# WemosESP8266.net
KiCad netlist of a schematic drawn in Altium Designer
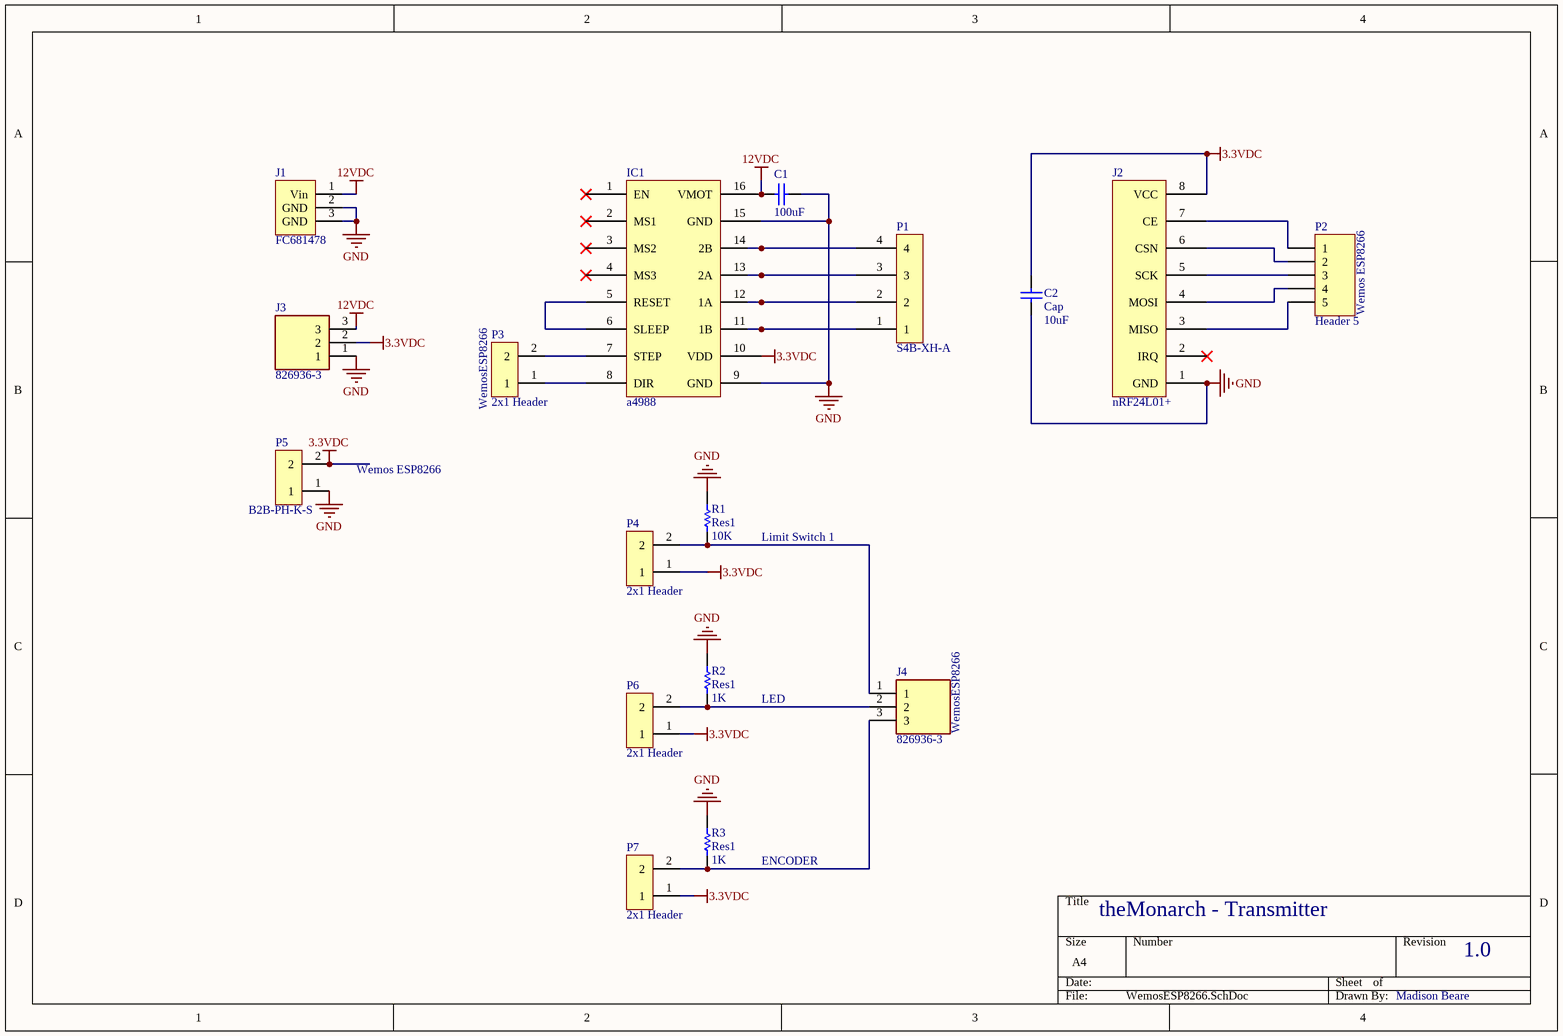
[diagram p0: WemosESP8266.SchDoc]

(export (version "E")
  (design (tool "Eeschema 10.0.6"))
  (components
    (comp (ref "C1")
      (value "100uF")
      (footprint "RAD-0.3")
      (description "Capacitor")
      (fields (field (name "PUBLISHER") "Altium Limited"))
      (libsource (lib "Miscellaneous Devices") (part "Cap"))
    )
    (comp (ref "C2")
      (value "Cap")
      (footprint "RAD-0.3")
      (description "Capacitor")
      (fields (field (name "ALTIUM_VALUE") "10uF") (field (name "PUBLISHER") "Altium Limited"))
      (libsource (lib "Miscellaneous Devices") (part "Cap"))
    )
    (comp (ref "IC1")
      (value "a4988")
      (footprint "MODULE_A4988_STEPPER_MOTOR_DRIVER_CARRIER")
      (libsource (lib "WemosESP8266_SchLib") (part "a4988"))
    )
    (comp (ref "J1")
      (value "FC681478")
      (footprint "FC681478")
      (description "CLIFF ELECTRONIC COMPONENTS         FC681478            CONNECTOR, POWER ENTRY, RCPT, 2A, 16VDC")
      (fields (field (name "MANUFACTURER") "Cliff"))
      (libsource (lib "WemosESP8266_SchLib") (part "FC681478"))
    )
    (comp (ref "J2")
      (value "nRF24L01+")
      (footprint "TE_5-146278-8")
      (description "SPARKFUN TRANSCEIVER BREAKOUT -")
      (fields (field (name "MANUFACTURER") "SparkFun") (field (name "MANUFACTURER PART NUMBER") "WRL-00691"))
      (libsource (lib "WemosESP8266_SchLib") (part "WRL-00691"))
    )
    (comp (ref "J3")
      (value "826936-3")
      (footprint "TE_826936-3")
      (description "Connector Header Through Hole 3 position 0.100 (2.54mm)")
      (fields (field (name "MF") "TE Connectivity"))
      (libsource (lib "") (part "826936-3_1"))
    )
    (comp (ref "J4")
      (value "826936-3")
      (footprint "TE_826936-3")
      (description "Connector Header Through Hole 3 position 0.100 (2.54mm)")
      (fields (field (name "MF") "TE Connectivity"))
      (libsource (lib "826936-3") (part "826936-3"))
    )
    (comp (ref "P1")
      (value "S4B-XH-A")
      (footprint "S4B-XH-A(LF)(SN)")
      (description "Conn Shrouded Header HDR 4 POS 2.5mm Solder RA Thru-Hole Box")
      (fields
        (field (name "MANUFACTURER") "JST")
        (field (name "MANUFACTURER PART NUMBER") "S4B-XH-A(LF)(SN)")
      )
      (libsource (lib "WemosESP8266_SchLib") (part "S4B-XH-A(LF)(SN)"))
    )
    (comp (ref "P2")
      (value "Header 5")
      (footprint "HDR1X5")
      (description "Header, 5-Pin")
      (fields (field (name "PUBLISHER") "Altium Limited"))
      (libsource (lib "Miscellaneous Connectors") (part "Header 5"))
    )
    (comp (ref "P3")
      (value "2x1 Header")
      (footprint "JST_S2B-XH-A(LF)(SN)")
      (description "Conn Shrouded Header HDR 2 POS 2.5mm Solder RA Thru-Hole Box")
      (fields
        (field (name "MANUFACTURER") "JST")
        (field (name "MANUFACTURER PART NUMBER") "S2B-XH-A(LF)(SN)")
      )
      (libsource (lib "WemosESP8266_SchLib") (part "S2B-XH-A(LF)(SN)"))
    )
    (comp (ref "P4")
      (value "2x1 Header")
      (footprint "JST_S2B-XH-A(LF)(SN)")
      (description "Conn Shrouded Header HDR 2 POS 2.5mm Solder RA Thru-Hole Box")
      (fields
        (field (name "MANUFACTURER") "JST")
        (field (name "MANUFACTURER PART NUMBER") "S2B-XH-A(LF)(SN)")
      )
      (libsource (lib "WemosESP8266_SchLib") (part "S2B-XH-A(LF)(SN)"))
    )
    (comp (ref "P5")
      (value "B2B-PH-K-S")
      (footprint "JST_B2B-PH-K-S(LF)(SN)")
      (description "Connector Header, PH Series, 2 Position, 2.00mm, Through Hole, Press-Fit, Solder, Natural")
      (fields
        (field (name "MANUFACTURER") "JST")
        (field (name "MANUFACTURER PART NUMBER") "B2B-PH-K-S(LF)(SN)")
      )
      (libsource (lib "WemosESP8266_SchLib") (part "B2B-PH-K-S(LF)(SN)"))
    )
    (comp (ref "P6")
      (value "2x1 Header")
      (footprint "JST_S2B-XH-A(LF)(SN)")
      (description "Conn Shrouded Header HDR 2 POS 2.5mm Solder RA Thru-Hole Box")
      (fields
        (field (name "MANUFACTURER") "JST")
        (field (name "MANUFACTURER PART NUMBER") "S2B-XH-A(LF)(SN)")
      )
      (libsource (lib "WemosESP8266_SchLib") (part "S2B-XH-A(LF)(SN)"))
    )
    (comp (ref "P7")
      (value "2x1 Header")
      (footprint "JST_S2B-XH-A(LF)(SN)")
      (description "Conn Shrouded Header HDR 2 POS 2.5mm Solder RA Thru-Hole Box")
      (fields
        (field (name "MANUFACTURER") "JST")
        (field (name "MANUFACTURER PART NUMBER") "S2B-XH-A(LF)(SN)")
      )
      (libsource (lib "WemosESP8266_SchLib") (part "S2B-XH-A(LF)(SN)"))
    )
    (comp (ref "R1")
      (value "Res1")
      (footprint "AXIAL-0.3")
      (description "Resistor")
      (fields (field (name "ALTIUM_VALUE") "10K") (field (name "PUBLISHER") "Altium Limited"))
      (libsource (lib "Miscellaneous Devices") (part "Res1"))
    )
    (comp (ref "R2")
      (value "Res1")
      (footprint "AXIAL-0.3")
      (description "Resistor")
      (fields (field (name "ALTIUM_VALUE") "1K") (field (name "PUBLISHER") "Altium Limited"))
      (libsource (lib "Miscellaneous Devices") (part "Res1"))
    )
    (comp (ref "R3")
      (value "Res1")
      (footprint "AXIAL-0.3")
      (description "Resistor")
      (fields (field (name "ALTIUM_VALUE") "1K") (field (name "PUBLISHER") "Altium Limited"))
      (libsource (lib "Miscellaneous Devices") (part "Res1"))
    )
  )
  (nets
    (net (code "1") (name "3.3VDC") (class "Default")
      (node (ref "C2") (pin "2") (pinfunction "2_2") (pintype "passive"))
      (node (ref "IC1") (pin "10") (pinfunction "VDD_10") (pintype "passive"))
      (node (ref "J2") (pin "8") (pinfunction "VCC_8") (pintype "passive"))
      (node (ref "J3") (pin "2") (pinfunction "2_2") (pintype "passive"))
      (node (ref "P4") (pin "1") (pinfunction "1_1") (pintype "passive"))
      (node (ref "P5") (pin "2") (pinfunction "2_2") (pintype "passive"))
      (node (ref "P6") (pin "1") (pinfunction "1_1") (pintype "passive"))
      (node (ref "P7") (pin "1") (pinfunction "1_1") (pintype "passive"))
    )
    (net (code "2") (name "12VDC") (class "Default")
      (node (ref "C1") (pin "1") (pinfunction "1_1") (pintype "passive"))
      (node (ref "IC1") (pin "16") (pinfunction "VMOT_16") (pintype "passive"))
      (node (ref "J1") (pin "1") (pinfunction "Vin_1") (pintype "passive"))
      (node (ref "J3") (pin "3") (pinfunction "3_3") (pintype "passive"))
    )
    (net (code "3") (name "GND") (class "Default")
      (node (ref "C1") (pin "2") (pinfunction "2_2") (pintype "passive"))
      (node (ref "C2") (pin "1") (pinfunction "1_1") (pintype "passive"))
      (node (ref "IC1") (pin "15") (pinfunction "GND_15") (pintype "passive"))
      (node (ref "IC1") (pin "9") (pinfunction "GND_9") (pintype "passive"))
      (node (ref "J1") (pin "2") (pinfunction "GND_2") (pintype "passive"))
      (node (ref "J1") (pin "3") (pinfunction "GND_3") (pintype "passive"))
      (node (ref "J2") (pin "1") (pinfunction "GND_1") (pintype "passive"))
      (node (ref "J3") (pin "1") (pinfunction "1_1") (pintype "passive"))
      (node (ref "P5") (pin "1") (pinfunction "1_1") (pintype "passive"))
      (node (ref "R1") (pin "2") (pinfunction "2_2") (pintype "passive"))
      (node (ref "R2") (pin "2") (pinfunction "2_2") (pintype "passive"))
      (node (ref "R3") (pin "2") (pinfunction "2_2") (pintype "passive"))
    )
    (net (code "4") (name "Net-(IC1-1A)") (class "Default")
      (node (ref "IC1") (pin "12") (pinfunction "1A_12") (pintype "passive"))
      (node (ref "P1") (pin "2") (pinfunction "2_2") (pintype "passive"))
    )
    (net (code "5") (name "Net-(IC1-1B)") (class "Default")
      (node (ref "IC1") (pin "11") (pinfunction "1B_11") (pintype "passive"))
      (node (ref "P1") (pin "1") (pinfunction "1_1") (pintype "passive"))
    )
    (net (code "6") (name "Net-(IC1-2A)") (class "Default")
      (node (ref "IC1") (pin "13") (pinfunction "2A_13") (pintype "passive"))
      (node (ref "P1") (pin "3") (pinfunction "3_3") (pintype "passive"))
    )
    (net (code "7") (name "Net-(IC1-2B)") (class "Default")
      (node (ref "IC1") (pin "14") (pinfunction "2B_14") (pintype "passive"))
      (node (ref "P1") (pin "4") (pinfunction "4_4") (pintype "passive"))
    )
    (net (code "8") (name "Net-(IC1-DIR)") (class "Default")
      (node (ref "IC1") (pin "8") (pinfunction "DIR_8") (pintype "passive"))
      (node (ref "P3") (pin "1") (pinfunction "1_1") (pintype "passive"))
    )
    (net (code "9") (name "Net-(IC1-RESET)") (class "Default")
      (node (ref "IC1") (pin "5") (pinfunction "RESET_5") (pintype "passive"))
      (node (ref "IC1") (pin "6") (pinfunction "SLEEP_6") (pintype "passive"))
    )
    (net (code "10") (name "Net-(IC1-STEP)") (class "Default")
      (node (ref "IC1") (pin "7") (pinfunction "STEP_7") (pintype "passive"))
      (node (ref "P3") (pin "2") (pinfunction "2_2") (pintype "passive"))
    )
    (net (code "11") (name "Net-(J2-CE)") (class "Default")
      (node (ref "J2") (pin "7") (pinfunction "CE_7") (pintype "passive"))
      (node (ref "P2") (pin "1") (pinfunction "1_1") (pintype "passive"))
    )
    (net (code "12") (name "Net-(J2-CSN)") (class "Default")
      (node (ref "J2") (pin "6") (pinfunction "CSN_6") (pintype "passive"))
      (node (ref "P2") (pin "2") (pinfunction "2_2") (pintype "passive"))
    )
    (net (code "13") (name "Net-(J2-MISO)") (class "Default")
      (node (ref "J2") (pin "3") (pinfunction "MISO_3") (pintype "passive"))
      (node (ref "P2") (pin "5") (pinfunction "5_5") (pintype "passive"))
    )
    (net (code "14") (name "Net-(J2-MOSI)") (class "Default")
      (node (ref "J2") (pin "4") (pinfunction "MOSI_4") (pintype "passive"))
      (node (ref "P2") (pin "4") (pinfunction "4_4") (pintype "passive"))
    )
    (net (code "15") (name "Net-(J2-SCK)") (class "Default")
      (node (ref "J2") (pin "5") (pinfunction "SCK_5") (pintype "passive"))
      (node (ref "P2") (pin "3") (pinfunction "3_3") (pintype "passive"))
    )
    (net (code "16") (name "Net-(J4-Pad1)") (class "Default")
      (node (ref "J4") (pin "1") (pinfunction "1_1") (pintype "passive"))
      (node (ref "P4") (pin "2") (pinfunction "2_2") (pintype "passive"))
      (node (ref "R1") (pin "1") (pinfunction "1_1") (pintype "passive"))
    )
    (net (code "17") (name "Net-(J4-Pad2)") (class "Default")
      (node (ref "J4") (pin "2") (pinfunction "2_2") (pintype "passive"))
      (node (ref "P6") (pin "2") (pinfunction "2_2") (pintype "passive"))
      (node (ref "R2") (pin "1") (pinfunction "1_1") (pintype "passive"))
    )
    (net (code "18") (name "Net-(J4-Pad3)") (class "Default")
      (node (ref "J4") (pin "3") (pinfunction "3_3") (pintype "passive"))
      (node (ref "P7") (pin "2") (pinfunction "2_2") (pintype "passive"))
      (node (ref "R3") (pin "1") (pinfunction "1_1") (pintype "passive"))
    )
    (net (code "19") (name "unconnected-(IC1-EN-Pad1)") (class "Default")
      (node (ref "IC1") (pin "1") (pinfunction "EN_1") (pintype "passive+no_connect"))
    )
    (net (code "20") (name "unconnected-(IC1-MS1-Pad2)") (class "Default")
      (node (ref "IC1") (pin "2") (pinfunction "MS1_2") (pintype "passive+no_connect"))
    )
    (net (code "21") (name "unconnected-(IC1-MS2-Pad3)") (class "Default")
      (node (ref "IC1") (pin "3") (pinfunction "MS2_3") (pintype "passive+no_connect"))
    )
    (net (code "22") (name "unconnected-(IC1-MS3-Pad4)") (class "Default")
      (node (ref "IC1") (pin "4") (pinfunction "MS3_4") (pintype "passive+no_connect"))
    )
    (net (code "23") (name "unconnected-(J2-IRQ-Pad2)") (class "Default")
      (node (ref "J2") (pin "2") (pinfunction "IRQ_2") (pintype "passive+no_connect"))
    )
  )
)
